# Sheet1.net
KiCad netlist of a schematic drawn in Altium Designer
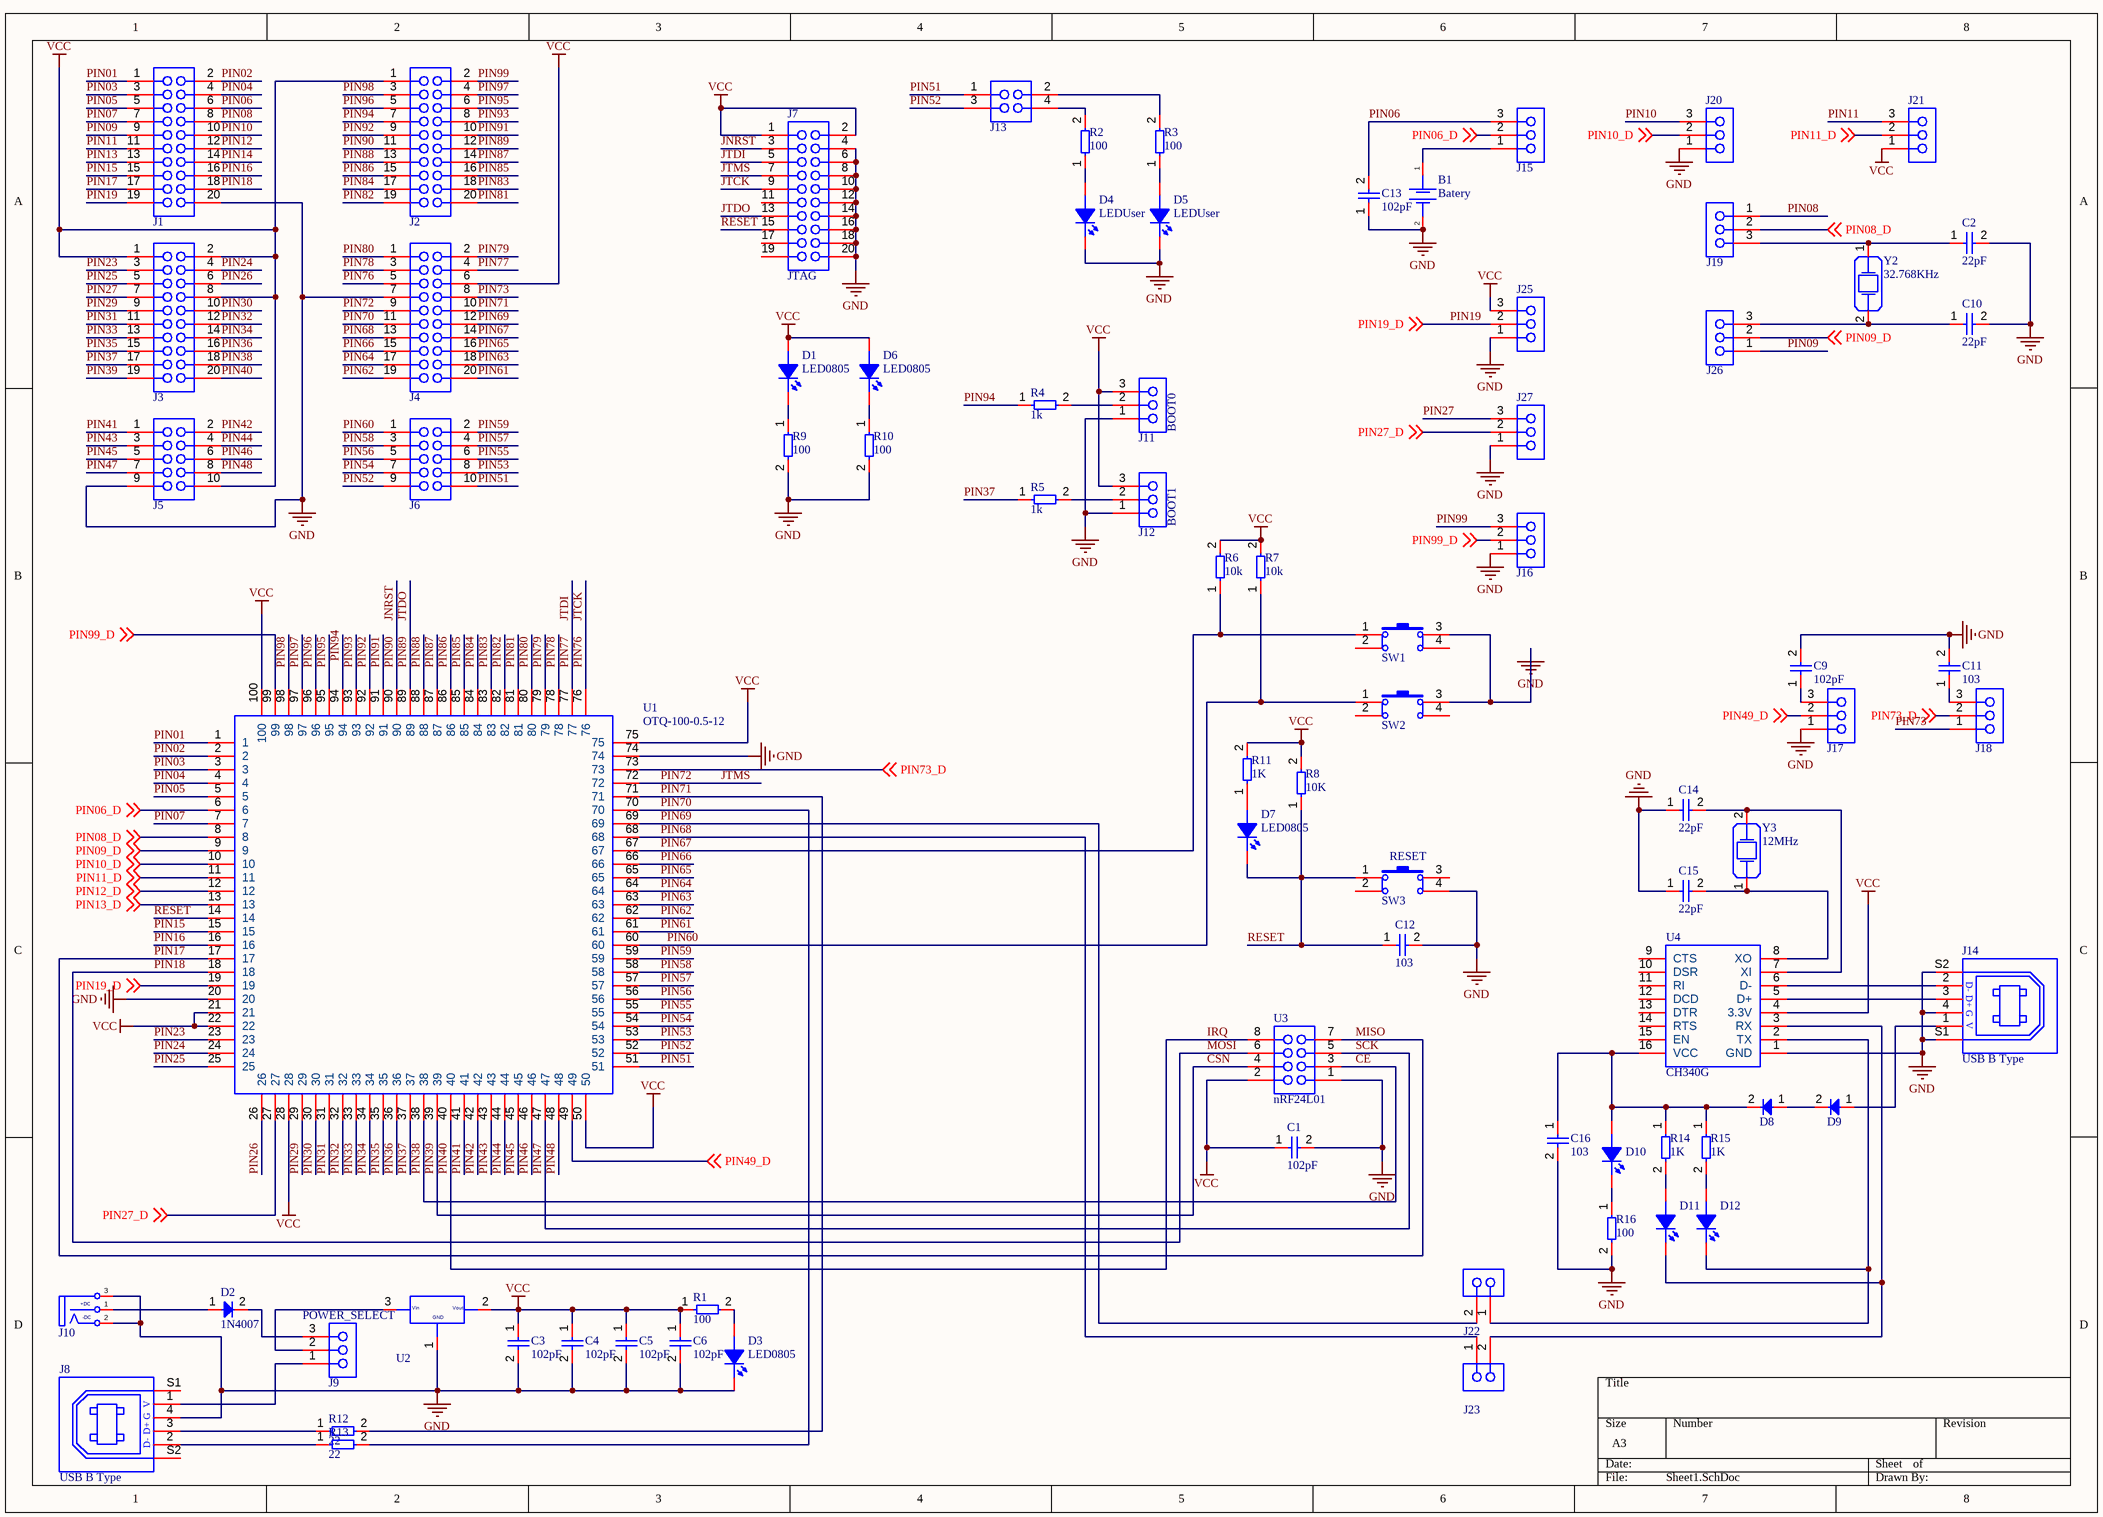
[diagram p0: Sheet1.SchDoc]

(export (version "E")
  (design (tool "Eeschema 10.0.6"))
  (components
    (comp (ref "B1") (value "Batery") (footprint "CR1220") (libsource (lib "SMDLibrary") (part "Batery")))
    (comp (ref "C1")
      (value "102pF")
      (footprint "C1206")
      (libsource (lib "SMDLibrary") (part "Capacitors(SMD)"))
    )
    (comp (ref "C2") (value "22pF") (footprint "C0805") (libsource (lib "SMDLibrary") (part "C0805")))
    (comp (ref "C3")
      (value "102pF")
      (footprint "C0805")
      (libsource (lib "SMDLibrary") (part "Capacitors(SMD)"))
    )
    (comp (ref "C4")
      (value "102pF")
      (footprint "C0805")
      (libsource (lib "SMDLibrary") (part "Capacitors(SMD)"))
    )
    (comp (ref "C5")
      (value "102pF")
      (footprint "C0805")
      (libsource (lib "SMDLibrary") (part "Capacitors(SMD)"))
    )
    (comp (ref "C6")
      (value "102pF")
      (footprint "C0805")
      (libsource (lib "SMDLibrary") (part "Capacitors(SMD)"))
    )
    (comp (ref "C9")
      (value "102pF")
      (footprint "C0805")
      (libsource (lib "SMDLibrary") (part "Capacitors(SMD)"))
    )
    (comp (ref "C10") (value "22pF") (footprint "C0805") (libsource (lib "SMDLibrary") (part "C0805")))
    (comp (ref "C11") (value "103") (footprint "C0805") (libsource (lib "SMDLibrary") (part "C0805")))
    (comp (ref "C12") (value "103") (footprint "C0805") (libsource (lib "SMDLibrary") (part "C0805")))
    (comp (ref "C13")
      (value "102pF")
      (footprint "C0805")
      (libsource (lib "SMDLibrary") (part "Capacitors(SMD)"))
    )
    (comp (ref "C14") (value "22pF") (footprint "C0805") (libsource (lib "SMDLibrary") (part "C0805")))
    (comp (ref "C15") (value "22pF") (footprint "C0805") (libsource (lib "SMDLibrary") (part "C0805")))
    (comp (ref "C16") (value "103") (footprint "C0805") (libsource (lib "SMDLibrary") (part "C0805")))
    (comp (ref "D1") (value "LED0805") (footprint "L0805RED") (libsource (lib "SMDLibrary") (part "LED0805")))
    (comp (ref "D2") (value "1N4007") (footprint "DO-41") (libsource (lib "SMDLibrary") (part "1N4007")))
    (comp (ref "D3") (value "LED0805") (footprint "L0805RED") (libsource (lib "SMDLibrary") (part "LED0805")))
    (comp (ref "D4") (value "LEDUser") (footprint "L0805RED") (libsource (lib "SMDLibrary") (part "LED0805")))
    (comp (ref "D5") (value "LEDUser") (footprint "L0805RED") (libsource (lib "SMDLibrary") (part "LED0805")))
    (comp (ref "D6") (value "LED0805") (footprint "L0805RED") (libsource (lib "SMDLibrary") (part "LED0805")))
    (comp (ref "D7") (value "LED0805") (footprint "L0805RED") (libsource (lib "SMDLibrary") (part "LED0805")))
    (comp (ref "D8")
      (value "1N4148")
      (footprint "SOD-80")
      (libsource (lib "SMDLibrary") (part "1N4148 (SOD-80)"))
    )
    (comp (ref "D9")
      (value "1N4148")
      (footprint "SOD-80")
      (libsource (lib "SMDLibrary") (part "1N4148 (SOD-80)"))
    )
    (comp (ref "D10")
      (value "LED0805")
      (footprint "L0805RED")
      (libsource (lib "SMDLibrary") (part "LED0805"))
    )
    (comp (ref "D11")
      (value "LED0805")
      (footprint "L0805RED")
      (libsource (lib "SMDLibrary") (part "LED0805"))
    )
    (comp (ref "D12")
      (value "LED0805")
      (footprint "L0805RED")
      (libsource (lib "SMDLibrary") (part "LED0805"))
    )
    (comp (ref "J1")
      (value "Header 10x2 TH Pitch 2.54mm")
      (footprint "Header 10x2 TH Pitch 2.54mm")
      (libsource (lib "SMDLibrary") (part "Header 10x2 TH Pitch 2.54mm"))
    )
    (comp (ref "J2")
      (value "Header 10x2 TH Pitch 2.54mm")
      (footprint "Header 10x2 TH Pitch 2.54mm")
      (libsource (lib "SMDLibrary") (part "Header 10x2 TH Pitch 2.54mm"))
    )
    (comp (ref "J3")
      (value "Header 10x2 TH Pitch 2.54mm")
      (footprint "Header 10x2 TH Pitch 2.54mm")
      (libsource (lib "SMDLibrary") (part "Header 10x2 TH Pitch 2.54mm"))
    )
    (comp (ref "J4")
      (value "Header 10x2 TH Pitch 2.54mm")
      (footprint "Header 10x2 TH Pitch 2.54mm")
      (libsource (lib "SMDLibrary") (part "Header 10x2 TH Pitch 2.54mm"))
    )
    (comp (ref "J5")
      (value "Header 5x2 TH Pitch 2.54mm")
      (footprint "Header 5x2 TH Pitch 2.54mm")
      (libsource (lib "SMDLibrary") (part "Header 5x2 TH Pitch 2.54mm"))
    )
    (comp (ref "J6")
      (value "Header 5x2 TH Pitch 2.54mm")
      (footprint "Header 5x2 TH Pitch 2.54mm")
      (libsource (lib "SMDLibrary") (part "Header 5x2 TH Pitch 2.54mm"))
    )
    (comp (ref "J7")
      (value "JTAG")
      (footprint "IDC_CONNECTOR_20_2.54")
      (libsource (lib "SMDLibrary") (part "IDC_2.54_10x2"))
    )
    (comp (ref "J8")
      (value "USB B Type")
      (footprint "USB-B-TYPE")
      (libsource (lib "SMDLibrary") (part "USB B Type"))
    )
    (comp (ref "J9")
      (value "POWER_SELECT")
      (footprint "Header 3x1 TH Pitch 2.54mm")
      (libsource (lib "SMDLibrary") (part "Header 3x1 TH Pitch 2.54mm"))
    )
    (comp (ref "J10")
      (value "Connector")
      (footprint "DC_JACK_161-0721")
      (libsource (lib "SMDLibrary") (part "JackDC"))
    )
    (comp (ref "J11")
      (value "BOOT0")
      (footprint "Header 3x1 TH Pitch 2.54mm")
      (libsource (lib "SMDLibrary") (part "Header 3x1 TH Pitch 2.54mm"))
    )
    (comp (ref "J12")
      (value "BOOT1")
      (footprint "Header 3x1 TH Pitch 2.54mm")
      (libsource (lib "SMDLibrary") (part "Header 3x1 TH Pitch 2.54mm"))
    )
    (comp (ref "J13")
      (value "Header 2x2 TH Pitch 2.54mm")
      (footprint "Header 2x2 TH Pitch 2.54mm")
      (libsource (lib "SMDLibrary") (part "Header 2x2 TH Pitch 2.54mm"))
    )
    (comp (ref "J14")
      (value "USB B Type")
      (footprint "USB-B-TYPE")
      (libsource (lib "") (part "USB B Type_1"))
    )
    (comp (ref "J15")
      (value "Header 3x1 TH Pitch 2.54mm")
      (footprint "Header 3x1 TH Pitch 2.54mm")
      (libsource (lib "SMDLibrary") (part "Header 3x1 TH Pitch 2.54mm"))
    )
    (comp (ref "J16")
      (value "Header 3x1 TH Pitch 2.54mm")
      (footprint "Header 3x1 TH Pitch 2.54mm")
      (libsource (lib "SMDLibrary") (part "Header 3x1 TH Pitch 2.54mm"))
    )
    (comp (ref "J17")
      (value "Header 3x1 TH Pitch 2.54mm")
      (footprint "Header 3x1 TH Pitch 2.54mm")
      (libsource (lib "SMDLibrary") (part "Header 3x1 TH Pitch 2.54mm"))
    )
    (comp (ref "J18")
      (value "Header 3x1 TH Pitch 2.54mm")
      (footprint "Header 3x1 TH Pitch 2.54mm")
      (libsource (lib "SMDLibrary") (part "Header 3x1 TH Pitch 2.54mm"))
    )
    (comp (ref "J19")
      (value "Header 3x1 TH Pitch 2.54mm")
      (footprint "Header 3x1 TH Pitch 2.54mm")
      (libsource (lib "") (part "Header 3x1 TH Pitch 2.54mm_1"))
    )
    (comp (ref "J20")
      (value "Header 3x1 TH Pitch 2.54mm")
      (footprint "Header 3x1 TH Pitch 2.54mm")
      (libsource (lib "SMDLibrary") (part "Header 3x1 TH Pitch 2.54mm"))
    )
    (comp (ref "J21")
      (value "Header 3x1 TH Pitch 2.54mm")
      (footprint "Header 3x1 TH Pitch 2.54mm")
      (libsource (lib "SMDLibrary") (part "Header 3x1 TH Pitch 2.54mm"))
    )
    (comp (ref "J22")
      (value "Header 2x1 TH Pitch 2.54mm")
      (footprint "Header 2x1 TH Pitch 2.54mm")
      (libsource (lib "") (part "Header 2x1 TH Pitch 2.54mm_1"))
    )
    (comp (ref "J23")
      (value "Header 2x1 TH Pitch 2.54mm")
      (footprint "Header 2x1 TH Pitch 2.54mm")
      (libsource (lib "SMDLibrary") (part "Header 2x1 TH Pitch 2.54mm"))
    )
    (comp (ref "J25")
      (value "Header 3x1 TH Pitch 2.54mm")
      (footprint "Header 3x1 TH Pitch 2.54mm")
      (libsource (lib "SMDLibrary") (part "Header 3x1 TH Pitch 2.54mm"))
    )
    (comp (ref "J26")
      (value "Header 3x1 TH Pitch 2.54mm")
      (footprint "Header 3x1 TH Pitch 2.54mm")
      (libsource (lib "") (part "Header 3x1 TH Pitch 2.54mm_2"))
    )
    (comp (ref "J27")
      (value "Header 3x1 TH Pitch 2.54mm")
      (footprint "Header 3x1 TH Pitch 2.54mm")
      (libsource (lib "SMDLibrary") (part "Header 3x1 TH Pitch 2.54mm"))
    )
    (comp (ref "R1") (value "100") (footprint "R0805") (libsource (lib "") (part "R0805_1")))
    (comp (ref "R2") (value "100") (footprint "R0805") (libsource (lib "SMDLibrary") (part "R0805")))
    (comp (ref "R3") (value "100") (footprint "R0805") (libsource (lib "SMDLibrary") (part "R0805")))
    (comp (ref "R4") (value "1k") (footprint "R0805") (libsource (lib "SMDLibrary") (part "Resistor SMD")))
    (comp (ref "R5") (value "1k") (footprint "R0805") (libsource (lib "SMDLibrary") (part "Resistor SMD")))
    (comp (ref "R6") (value "10k") (footprint "R0805") (libsource (lib "") (part "Resistor SMD_1")))
    (comp (ref "R7") (value "10k") (footprint "R0805") (libsource (lib "") (part "Resistor SMD_1")))
    (comp (ref "R8") (value "10K") (footprint "R0805") (libsource (lib "SMDLibrary") (part "R0805")))
    (comp (ref "R9") (value "100") (footprint "R0805") (libsource (lib "") (part "Resistor SMD_2")))
    (comp (ref "R10") (value "100") (footprint "R0805") (libsource (lib "") (part "Resistor SMD_2")))
    (comp (ref "R11") (value "1K") (footprint "R0805") (libsource (lib "") (part "Resistor SMD_1")))
    (comp (ref "R12") (value "22") (footprint "R0805") (libsource (lib "SMDLibrary") (part "Resistor SMD")))
    (comp (ref "R13") (value "22") (footprint "R0805") (libsource (lib "SMDLibrary") (part "Resistor SMD")))
    (comp (ref "R14") (value "1K") (footprint "R0805") (libsource (lib "") (part "R0805_2")))
    (comp (ref "R15") (value "1K") (footprint "R0805") (libsource (lib "") (part "R0805_2")))
    (comp (ref "R16") (value "100") (footprint "R0805") (libsource (lib "") (part "R0805_2")))
    (comp (ref "SW1")
      (value "Button Hole")
      (footprint "BUTTON_HOLE_5.0mm")
      (libsource (lib "SMDLibrary") (part "Button Hole"))
    )
    (comp (ref "SW2")
      (value "Button Hole")
      (footprint "BUTTON_HOLE_5.0mm")
      (libsource (lib "SMDLibrary") (part "Button Hole"))
    )
    (comp (ref "SW3")
      (value "RESET")
      (footprint "BUTTON_HOLE_5.0mm")
      (libsource (lib "SMDLibrary") (part "Button Hole"))
    )
    (comp (ref "U1")
      (value "OTQ-100-0.5-12")
      (footprint "ENPLAS OTQ-100-0.5-12")
      (libsource (lib "SMDLibrary") (part "ENPLAS OTQ-100-0.5-12"))
    )
    (comp (ref "U2")
      (value "AMS1117")
      (footprint "SOT223-3")
      (libsource (lib "SMDLibrary") (part "AMS1117(SOT-223)"))
    )
    (comp (ref "U3")
      (value "nRF24L01")
      (footprint "nRF24L01")
      (libsource (lib "SMDLibrary") (part "nRF24L01"))
    )
    (comp (ref "U4")
      (value "CH340G")
      (footprint "SOP16_1.27_3.8")
      (libsource (lib "SMDLibrary") (part "CH340G"))
    )
    (comp (ref "Y2")
      (value "32.768KHz")
      (footprint "DT-26")
      (libsource (lib "SMDLibrary") (part "Crystal 32.768KHz"))
    )
    (comp (ref "Y3") (value "12MHz") (footprint "SMD5032") (libsource (lib "SMDLibrary") (part "Crystal")))
  )
  (nets
    (net (code "1") (name "/CE") (class "Default")
      (node (ref "J3") (pin "18") (pinfunction "18_18") (pintype "passive"))
      (node (ref "U1") (pin "38") (pinfunction "38_38") (pintype "passive"))
      (node (ref "U3") (pin "3") (pinfunction "3_3") (pintype "passive"))
    )
    (net (code "2") (name "/CSN") (class "Default")
      (node (ref "J3") (pin "19") (pinfunction "19_19") (pintype "passive"))
      (node (ref "U1") (pin "39") (pinfunction "39_39") (pintype "passive"))
      (node (ref "U3") (pin "4") (pinfunction "4_4") (pintype "passive"))
    )
    (net (code "3") (name "/IRQ") (class "Default")
      (node (ref "J3") (pin "20") (pinfunction "20_20") (pintype "passive"))
      (node (ref "U1") (pin "40") (pinfunction "40_40") (pintype "passive"))
      (node (ref "U3") (pin "8") (pinfunction "8_8") (pintype "passive"))
    )
    (net (code "4") (name "/JNRST") (class "Default")
      (node (ref "J2") (pin "11") (pinfunction "11_11") (pintype "passive"))
      (node (ref "J7") (pin "3") (pinfunction "3_3") (pintype "passive"))
      (node (ref "U1") (pin "90") (pinfunction "90_90") (pintype "passive"))
    )
    (net (code "5") (name "/JTCK") (class "Default")
      (node (ref "J4") (pin "5") (pinfunction "5_5") (pintype "passive"))
      (node (ref "J7") (pin "9") (pinfunction "9_9") (pintype "passive"))
      (node (ref "U1") (pin "76") (pinfunction "76_76") (pintype "passive"))
    )
    (net (code "6") (name "/JTDI") (class "Default")
      (node (ref "J4") (pin "4") (pinfunction "4_4") (pintype "passive"))
      (node (ref "J7") (pin "5") (pinfunction "5_5") (pintype "passive"))
      (node (ref "U1") (pin "77") (pinfunction "77_77") (pintype "passive"))
    )
    (net (code "7") (name "/JTDO") (class "Default")
      (node (ref "J2") (pin "12") (pinfunction "12_12") (pintype "passive"))
      (node (ref "J7") (pin "13") (pinfunction "13_13") (pintype "passive"))
      (node (ref "U1") (pin "89") (pinfunction "89_89") (pintype "passive"))
    )
    (net (code "8") (name "/JTMS") (class "Default")
      (node (ref "J4") (pin "9") (pinfunction "9_9") (pintype "passive"))
      (node (ref "J7") (pin "7") (pinfunction "7_7") (pintype "passive"))
      (node (ref "U1") (pin "72") (pinfunction "72_72") (pintype "passive"))
    )
    (net (code "9") (name "/MISO") (class "Default")
      (node (ref "J1") (pin "17") (pinfunction "17_17") (pintype "passive"))
      (node (ref "U1") (pin "17") (pinfunction "17_17") (pintype "passive"))
      (node (ref "U3") (pin "7") (pinfunction "7_7") (pintype "passive"))
    )
    (net (code "10") (name "/MOSI") (class "Default")
      (node (ref "J1") (pin "18") (pinfunction "18_18") (pintype "passive"))
      (node (ref "U1") (pin "18") (pinfunction "18_18") (pintype "passive"))
      (node (ref "U3") (pin "6") (pinfunction "6_6") (pintype "passive"))
    )
    (net (code "11") (name "/PIN01") (class "Default")
      (node (ref "J1") (pin "1") (pinfunction "1_1") (pintype "passive"))
      (node (ref "U1") (pin "1") (pinfunction "1_1") (pintype "passive"))
    )
    (net (code "12") (name "/PIN02") (class "Default")
      (node (ref "J1") (pin "2") (pinfunction "2_2") (pintype "passive"))
      (node (ref "U1") (pin "2") (pinfunction "2_2") (pintype "passive"))
    )
    (net (code "13") (name "/PIN03") (class "Default")
      (node (ref "J1") (pin "3") (pinfunction "3_3") (pintype "passive"))
      (node (ref "U1") (pin "3") (pinfunction "3_3") (pintype "passive"))
    )
    (net (code "14") (name "/PIN04") (class "Default")
      (node (ref "J1") (pin "4") (pinfunction "4_4") (pintype "passive"))
      (node (ref "U1") (pin "4") (pinfunction "4_4") (pintype "passive"))
    )
    (net (code "15") (name "/PIN05") (class "Default")
      (node (ref "J1") (pin "5") (pinfunction "5_5") (pintype "passive"))
      (node (ref "U1") (pin "5") (pinfunction "5_5") (pintype "passive"))
    )
    (net (code "16") (name "/PIN06") (class "Default")
      (node (ref "C13") (pin "2") (pinfunction "2_2") (pintype "passive"))
      (node (ref "J1") (pin "6") (pinfunction "6_6") (pintype "passive"))
      (node (ref "J15") (pin "3") (pinfunction "3_3") (pintype "passive"))
    )
    (net (code "17") (name "/PIN07") (class "Default")
      (node (ref "J1") (pin "7") (pinfunction "7_7") (pintype "passive"))
      (node (ref "U1") (pin "7") (pinfunction "7_7") (pintype "passive"))
    )
    (net (code "18") (name "/PIN08") (class "Default")
      (node (ref "J1") (pin "8") (pinfunction "8_8") (pintype "passive"))
      (node (ref "J19") (pin "1") (pinfunction "1_1") (pintype "passive"))
    )
    (net (code "19") (name "/PIN09") (class "Default")
      (node (ref "J1") (pin "9") (pinfunction "9_9") (pintype "passive"))
      (node (ref "J26") (pin "1") (pinfunction "1_1") (pintype "passive"))
    )
    (net (code "20") (name "/PIN10") (class "Default")
      (node (ref "J1") (pin "10") (pinfunction "10_10") (pintype "passive"))
      (node (ref "J20") (pin "3") (pinfunction "3_3") (pintype "passive"))
    )
    (net (code "21") (name "/PIN11") (class "Default")
      (node (ref "J1") (pin "11") (pinfunction "11_11") (pintype "passive"))
      (node (ref "J21") (pin "3") (pinfunction "3_3") (pintype "passive"))
    )
    (net (code "22") (name "/PIN12") (class "Default")
      (node (ref "J1") (pin "12") (pinfunction "12_12") (pintype "passive"))
    )
    (net (code "23") (name "/PIN13") (class "Default")
      (node (ref "J1") (pin "13") (pinfunction "13_13") (pintype "passive"))
    )
    (net (code "24") (name "/PIN14") (class "Default")
      (node (ref "J1") (pin "14") (pinfunction "14_14") (pintype "passive"))
    )
    (net (code "25") (name "/PIN15") (class "Default")
      (node (ref "J1") (pin "15") (pinfunction "15_15") (pintype "passive"))
      (node (ref "U1") (pin "15") (pinfunction "15_15") (pintype "passive"))
    )
    (net (code "26") (name "/PIN16") (class "Default")
      (node (ref "J1") (pin "16") (pinfunction "16_16") (pintype "passive"))
      (node (ref "U1") (pin "16") (pinfunction "16_16") (pintype "passive"))
    )
    (net (code "27") (name "/PIN23") (class "Default")
      (node (ref "J3") (pin "3") (pinfunction "3_3") (pintype "passive"))
      (node (ref "U1") (pin "23") (pinfunction "23_23") (pintype "passive"))
    )
    (net (code "28") (name "/PIN24") (class "Default")
      (node (ref "J3") (pin "4") (pinfunction "4_4") (pintype "passive"))
      (node (ref "U1") (pin "24") (pinfunction "24_24") (pintype "passive"))
    )
    (net (code "29") (name "/PIN25") (class "Default")
      (node (ref "J3") (pin "5") (pinfunction "5_5") (pintype "passive"))
      (node (ref "U1") (pin "25") (pinfunction "25_25") (pintype "passive"))
    )
    (net (code "30") (name "/PIN26") (class "Default")
      (node (ref "J3") (pin "6") (pinfunction "6_6") (pintype "passive"))
      (node (ref "U1") (pin "26") (pinfunction "26_26") (pintype "passive"))
    )
    (net (code "31") (name "/PIN27") (class "Default")
      (node (ref "J27") (pin "3") (pinfunction "3_3") (pintype "passive"))
      (node (ref "J3") (pin "7") (pinfunction "7_7") (pintype "passive"))
    )
    (net (code "32") (name "/PIN29") (class "Default")
      (node (ref "J3") (pin "9") (pinfunction "9_9") (pintype "passive"))
      (node (ref "U1") (pin "29") (pinfunction "29_29") (pintype "passive"))
    )
    (net (code "33") (name "/PIN30") (class "Default")
      (node (ref "J3") (pin "10") (pinfunction "10_10") (pintype "passive"))
      (node (ref "U1") (pin "30") (pinfunction "30_30") (pintype "passive"))
    )
    (net (code "34") (name "/PIN31") (class "Default")
      (node (ref "J3") (pin "11") (pinfunction "11_11") (pintype "passive"))
      (node (ref "U1") (pin "31") (pinfunction "31_31") (pintype "passive"))
    )
    (net (code "35") (name "/PIN32") (class "Default")
      (node (ref "J3") (pin "12") (pinfunction "12_12") (pintype "passive"))
      (node (ref "U1") (pin "32") (pinfunction "32_32") (pintype "passive"))
    )
    (net (code "36") (name "/PIN33") (class "Default")
      (node (ref "J3") (pin "13") (pinfunction "13_13") (pintype "passive"))
      (node (ref "U1") (pin "33") (pinfunction "33_33") (pintype "passive"))
    )
    (net (code "37") (name "/PIN34") (class "Default")
      (node (ref "J3") (pin "14") (pinfunction "14_14") (pintype "passive"))
      (node (ref "U1") (pin "34") (pinfunction "34_34") (pintype "passive"))
    )
    (net (code "38") (name "/PIN35") (class "Default")
      (node (ref "J3") (pin "15") (pinfunction "15_15") (pintype "passive"))
      (node (ref "U1") (pin "35") (pinfunction "35_35") (pintype "passive"))
    )
    (net (code "39") (name "/PIN36") (class "Default")
      (node (ref "J3") (pin "16") (pinfunction "16_16") (pintype "passive"))
      (node (ref "U1") (pin "36") (pinfunction "36_36") (pintype "passive"))
    )
    (net (code "40") (name "/PIN37") (class "Default")
      (node (ref "J3") (pin "17") (pinfunction "17_17") (pintype "passive"))
      (node (ref "R5") (pin "1") (pinfunction "1_1") (pintype "passive"))
      (node (ref "U1") (pin "37") (pinfunction "37_37") (pintype "passive"))
    )
    (net (code "41") (name "/PIN41") (class "Default")
      (node (ref "J5") (pin "1") (pinfunction "1_1") (pintype "passive"))
      (node (ref "U1") (pin "41") (pinfunction "41_41") (pintype "passive"))
    )
    (net (code "42") (name "/PIN42") (class "Default")
      (node (ref "J5") (pin "2") (pinfunction "2_2") (pintype "passive"))
      (node (ref "U1") (pin "42") (pinfunction "42_42") (pintype "passive"))
    )
    (net (code "43") (name "/PIN43") (class "Default")
      (node (ref "J5") (pin "3") (pinfunction "3_3") (pintype "passive"))
      (node (ref "U1") (pin "43") (pinfunction "43_43") (pintype "passive"))
    )
    (net (code "44") (name "/PIN44") (class "Default")
      (node (ref "J5") (pin "4") (pinfunction "4_4") (pintype "passive"))
      (node (ref "U1") (pin "44") (pinfunction "44_44") (pintype "passive"))
    )
    (net (code "45") (name "/PIN45") (class "Default")
      (node (ref "J5") (pin "5") (pinfunction "5_5") (pintype "passive"))
      (node (ref "U1") (pin "45") (pinfunction "45_45") (pintype "passive"))
    )
    (net (code "46") (name "/PIN46") (class "Default")
      (node (ref "J5") (pin "6") (pinfunction "6_6") (pintype "passive"))
      (node (ref "U1") (pin "46") (pinfunction "46_46") (pintype "passive"))
    )
    (net (code "47") (name "/PIN47") (class "Default")
      (node (ref "J5") (pin "7") (pinfunction "7_7") (pintype "passive"))
      (node (ref "U1") (pin "47") (pinfunction "47_47") (pintype "passive"))
      (node (ref "U3") (pin "5") (pinfunction "5_5") (pintype "passive"))
    )
    (net (code "48") (name "/PIN48") (class "Default")
      (node (ref "J5") (pin "8") (pinfunction "8_8") (pintype "passive"))
      (node (ref "U1") (pin "48") (pinfunction "48_48") (pintype "passive"))
    )
    (net (code "49") (name "/PIN51") (class "Default")
      (node (ref "J13") (pin "1") (pinfunction "1_1") (pintype "passive"))
      (node (ref "J6") (pin "10") (pinfunction "10_10") (pintype "passive"))
      (node (ref "U1") (pin "51") (pinfunction "51_51") (pintype "passive"))
    )
    (net (code "50") (name "/PIN52") (class "Default")
      (node (ref "J13") (pin "3") (pinfunction "3_3") (pintype "passive"))
      (node (ref "J6") (pin "9") (pinfunction "9_9") (pintype "passive"))
      (node (ref "U1") (pin "52") (pinfunction "52_52") (pintype "passive"))
    )
    (net (code "51") (name "/PIN53") (class "Default")
      (node (ref "J6") (pin "8") (pinfunction "8_8") (pintype "passive"))
      (node (ref "U1") (pin "53") (pinfunction "53_53") (pintype "passive"))
    )
    (net (code "52") (name "/PIN54") (class "Default")
      (node (ref "J6") (pin "7") (pinfunction "7_7") (pintype "passive"))
      (node (ref "U1") (pin "54") (pinfunction "54_54") (pintype "passive"))
    )
    (net (code "53") (name "/PIN55") (class "Default")
      (node (ref "J6") (pin "6") (pinfunction "6_6") (pintype "passive"))
      (node (ref "U1") (pin "55") (pinfunction "55_55") (pintype "passive"))
    )
    (net (code "54") (name "/PIN56") (class "Default")
      (node (ref "J6") (pin "5") (pinfunction "5_5") (pintype "passive"))
      (node (ref "U1") (pin "56") (pinfunction "56_56") (pintype "passive"))
    )
    (net (code "55") (name "/PIN57") (class "Default")
      (node (ref "J6") (pin "4") (pinfunction "4_4") (pintype "passive"))
      (node (ref "U1") (pin "57") (pinfunction "57_57") (pintype "passive"))
    )
    (net (code "56") (name "/PIN58") (class "Default")
      (node (ref "J6") (pin "3") (pinfunction "3_3") (pintype "passive"))
      (node (ref "U1") (pin "58") (pinfunction "58_58") (pintype "passive"))
    )
    (net (code "57") (name "/PIN59") (class "Default")
      (node (ref "J6") (pin "2") (pinfunction "2_2") (pintype "passive"))
      (node (ref "U1") (pin "59") (pinfunction "59_59") (pintype "passive"))
    )
    (net (code "58") (name "/PIN60") (class "Default")
      (node (ref "J6") (pin "1") (pinfunction "1_1") (pintype "passive"))
      (node (ref "R7") (pin "1") (pinfunction "1_1") (pintype "passive"))
      (node (ref "SW2") (pin "1") (pinfunction "1_1") (pintype "passive"))
      (node (ref "U1") (pin "60") (pinfunction "60_60") (pintype "passive"))
    )
    (net (code "59") (name "/PIN61") (class "Default")
      (node (ref "J4") (pin "20") (pinfunction "20_20") (pintype "passive"))
      (node (ref "U1") (pin "61") (pinfunction "61_61") (pintype "passive"))
    )
    (net (code "60") (name "/PIN62") (class "Default")
      (node (ref "J4") (pin "19") (pinfunction "19_19") (pintype "passive"))
      (node (ref "U1") (pin "62") (pinfunction "62_62") (pintype "passive"))
    )
    (net (code "61") (name "/PIN63") (class "Default")
      (node (ref "J4") (pin "18") (pinfunction "18_18") (pintype "passive"))
      (node (ref "U1") (pin "63") (pinfunction "63_63") (pintype "passive"))
    )
    (net (code "62") (name "/PIN64") (class "Default")
      (node (ref "J4") (pin "17") (pinfunction "17_17") (pintype "passive"))
      (node (ref "U1") (pin "64") (pinfunction "64_64") (pintype "passive"))
    )
    (net (code "63") (name "/PIN65") (class "Default")
      (node (ref "J4") (pin "16") (pinfunction "16_16") (pintype "passive"))
      (node (ref "U1") (pin "65") (pinfunction "65_65") (pintype "passive"))
    )
    (net (code "64") (name "/PIN66") (class "Default")
      (node (ref "J4") (pin "15") (pinfunction "15_15") (pintype "passive"))
      (node (ref "U1") (pin "66") (pinfunction "66_66") (pintype "passive"))
    )
    (net (code "65") (name "/PIN67") (class "Default")
      (node (ref "J4") (pin "14") (pinfunction "14_14") (pintype "passive"))
      (node (ref "R6") (pin "1") (pinfunction "1_1") (pintype "passive"))
      (node (ref "SW1") (pin "1") (pinfunction "1_1") (pintype "passive"))
      (node (ref "U1") (pin "67") (pinfunction "67_67") (pintype "passive"))
    )
    (net (code "66") (name "/PIN68") (class "Default")
      (node (ref "J23") (pin "1") (pinfunction "1_1") (pintype "passive"))
      (node (ref "J4") (pin "13") (pinfunction "13_13") (pintype "passive"))
      (node (ref "U1") (pin "68") (pinfunction "68_68") (pintype "passive"))
    )
    (net (code "67") (name "/PIN69") (class "Default")
      (node (ref "J22") (pin "2") (pinfunction "2_2") (pintype "passive"))
      (node (ref "J4") (pin "12") (pinfunction "12_12") (pintype "passive"))
      (node (ref "U1") (pin "69") (pinfunction "69_69") (pintype "passive"))
    )
    (net (code "68") (name "/PIN70") (class "Default")
      (node (ref "J4") (pin "11") (pinfunction "11_11") (pintype "passive"))
      (node (ref "R13") (pin "2") (pinfunction "2_2") (pintype "passive"))
      (node (ref "U1") (pin "70") (pinfunction "70_70") (pintype "passive"))
    )
    (net (code "69") (name "/PIN71") (class "Default")
      (node (ref "J4") (pin "10") (pinfunction "10_10") (pintype "passive"))
      (node (ref "R12") (pin "2") (pinfunction "2_2") (pintype "passive"))
      (node (ref "U1") (pin "71") (pinfunction "71_71") (pintype "passive"))
    )
    (net (code "70") (name "/PIN73") (class "Default")
      (node (ref "J18") (pin "1") (pinfunction "1_1") (pintype "passive"))
      (node (ref "J4") (pin "8") (pinfunction "8_8") (pintype "passive"))
    )
    (net (code "71") (name "/PIN78") (class "Default")
      (node (ref "J4") (pin "3") (pinfunction "3_3") (pintype "passive"))
      (node (ref "U1") (pin "78") (pinfunction "78_78") (pintype "passive"))
    )
    (net (code "72") (name "/PIN79") (class "Default")
      (node (ref "J4") (pin "2") (pinfunction "2_2") (pintype "passive"))
      (node (ref "U1") (pin "79") (pinfunction "79_79") (pintype "passive"))
    )
    (net (code "73") (name "/PIN80") (class "Default")
      (node (ref "J4") (pin "1") (pinfunction "1_1") (pintype "passive"))
      (node (ref "U1") (pin "80") (pinfunction "80_80") (pintype "passive"))
    )
    (net (code "74") (name "/PIN81") (class "Default")
      (node (ref "J2") (pin "20") (pinfunction "20_20") (pintype "passive"))
      (node (ref "U1") (pin "81") (pinfunction "81_81") (pintype "passive"))
    )
    (net (code "75") (name "/PIN82") (class "Default")
      (node (ref "J2") (pin "19") (pinfunction "19_19") (pintype "passive"))
      (node (ref "U1") (pin "82") (pinfunction "82_82") (pintype "passive"))
    )
    (net (code "76") (name "/PIN83") (class "Default")
      (node (ref "J2") (pin "18") (pinfunction "18_18") (pintype "passive"))
      (node (ref "U1") (pin "83") (pinfunction "83_83") (pintype "passive"))
    )
    (net (code "77") (name "/PIN84") (class "Default")
      (node (ref "J2") (pin "17") (pinfunction "17_17") (pintype "passive"))
      (node (ref "U1") (pin "84") (pinfunction "84_84") (pintype "passive"))
    )
    (net (code "78") (name "/PIN85") (class "Default")
      (node (ref "J2") (pin "16") (pinfunction "16_16") (pintype "passive"))
      (node (ref "U1") (pin "85") (pinfunction "85_85") (pintype "passive"))
    )
    (net (code "79") (name "/PIN86") (class "Default")
      (node (ref "J2") (pin "15") (pinfunction "15_15") (pintype "passive"))
      (node (ref "U1") (pin "86") (pinfunction "86_86") (pintype "passive"))
    )
    (net (code "80") (name "/PIN87") (class "Default")
      (node (ref "J2") (pin "14") (pinfunction "14_14") (pintype "passive"))
      (node (ref "U1") (pin "87") (pinfunction "87_87") (pintype "passive"))
    )
    (net (code "81") (name "/PIN88") (class "Default")
      (node (ref "J2") (pin "13") (pinfunction "13_13") (pintype "passive"))
      (node (ref "U1") (pin "88") (pinfunction "88_88") (pintype "passive"))
    )
    (net (code "82") (name "/PIN91") (class "Default")
      (node (ref "J2") (pin "10") (pinfunction "10_10") (pintype "passive"))
      (node (ref "U1") (pin "91") (pinfunction "91_91") (pintype "passive"))
    )
    (net (code "83") (name "/PIN92") (class "Default")
      (node (ref "J2") (pin "9") (pinfunction "9_9") (pintype "passive"))
      (node (ref "U1") (pin "92") (pinfunction "92_92") (pintype "passive"))
    )
    (net (code "84") (name "/PIN93") (class "Default")
      (node (ref "J2") (pin "8") (pinfunction "8_8") (pintype "passive"))
      (node (ref "U1") (pin "93") (pinfunction "93_93") (pintype "passive"))
    )
    (net (code "85") (name "/PIN94") (class "Default")
      (node (ref "J2") (pin "7") (pinfunction "7_7") (pintype "passive"))
      (node (ref "R4") (pin "1") (pinfunction "1_1") (pintype "passive"))
      (node (ref "U1") (pin "94") (pinfunction "94_94") (pintype "passive"))
    )
    (net (code "86") (name "/PIN95") (class "Default")
      (node (ref "J2") (pin "6") (pinfunction "6_6") (pintype "passive"))
      (node (ref "U1") (pin "95") (pinfunction "95_95") (pintype "passive"))
    )
    (net (code "87") (name "/PIN96") (class "Default")
      (node (ref "J2") (pin "5") (pinfunction "5_5") (pintype "passive"))
      (node (ref "U1") (pin "96") (pinfunction "96_96") (pintype "passive"))
    )
    (net (code "88") (name "/PIN97") (class "Default")
      (node (ref "J2") (pin "4") (pinfunction "4_4") (pintype "passive"))
      (node (ref "U1") (pin "97") (pinfunction "97_97") (pintype "passive"))
    )
    (net (code "89") (name "/PIN98") (class "Default")
      (node (ref "J2") (pin "3") (pinfunction "3_3") (pintype "passive"))
      (node (ref "U1") (pin "98") (pinfunction "98_98") (pintype "passive"))
    )
    (net (code "90") (name "/PIN99") (class "Default")
      (node (ref "J16") (pin "3") (pinfunction "3_3") (pintype "passive"))
      (node (ref "J2") (pin "2") (pinfunction "2_2") (pintype "passive"))
    )
    (net (code "91") (name "/RESET") (class "Default")
      (node (ref "C12") (pin "1") (pinfunction "1_1") (pintype "passive"))
      (node (ref "D7") (pin "2") (pinfunction "K_2") (pintype "passive"))
      (node (ref "J7") (pin "15") (pinfunction "15_15") (pintype "passive"))
      (node (ref "R8") (pin "1") (pinfunction "1_1") (pintype "passive"))
      (node (ref "SW3") (pin "1") (pinfunction "1_1") (pintype "passive"))
      (node (ref "U1") (pin "14") (pinfunction "14_14") (pintype "passive"))
    )
    (net (code "92") (name "GND") (class "Default")
      (node (ref "B1") (pin "2") (pinfunction "2_2") (pintype "passive"))
      (node (ref "C1") (pin "2") (pinfunction "2_2") (pintype "passive"))
      (node (ref "C10") (pin "2") (pinfunction "2_2") (pintype "passive"))
      (node (ref "C11") (pin "2") (pinfunction "2_2") (pintype "passive"))
      (node (ref "C12") (pin "2") (pinfunction "2_2") (pintype "passive"))
      (node (ref "C13") (pin "1") (pinfunction "1_1") (pintype "passive"))
      (node (ref "C14") (pin "1") (pinfunction "1_1") (pintype "passive"))
      (node (ref "C15") (pin "1") (pinfunction "1_1") (pintype "passive"))
      (node (ref "C16") (pin "2") (pinfunction "2_2") (pintype "passive"))
      (node (ref "C2") (pin "2") (pinfunction "2_2") (pintype "passive"))
      (node (ref "C3") (pin "2") (pinfunction "2_2") (pintype "passive"))
      (node (ref "C4") (pin "2") (pinfunction "2_2") (pintype "passive"))
      (node (ref "C5") (pin "2") (pinfunction "2_2") (pintype "passive"))
      (node (ref "C6") (pin "2") (pinfunction "2_2") (pintype "passive"))
      (node (ref "C9") (pin "2") (pinfunction "2_2") (pintype "passive"))
      (node (ref "D3") (pin "2") (pinfunction "K_2") (pintype "passive"))
      (node (ref "D4") (pin "2") (pinfunction "K_2") (pintype "passive"))
      (node (ref "D5") (pin "2") (pinfunction "K_2") (pintype "passive"))
      (node (ref "J1") (pin "20") (pinfunction "20_20") (pintype "passive"))
      (node (ref "J10") (pin "2") (pinfunction "DC-_2") (pintype "passive"))
      (node (ref "J10") (pin "3") (pinfunction "T_3") (pintype "passive"))
      (node (ref "J11") (pin "1") (pinfunction "1_1") (pintype "passive"))
      (node (ref "J12") (pin "1") (pinfunction "1_1") (pintype "passive"))
      (node (ref "J14") (pin "4") (pinfunction "4_4") (pintype "passive"))
      (node (ref "J14") (pin "S1") (pinfunction "S1_S1") (pintype "passive"))
      (node (ref "J14") (pin "S2") (pinfunction "S2_S2") (pintype "passive"))
      (node (ref "J16") (pin "1") (pinfunction "1_1") (pintype "passive"))
      (node (ref "J17") (pin "1") (pinfunction "1_1") (pintype "passive"))
      (node (ref "J20") (pin "1") (pinfunction "1_1") (pintype "passive"))
      (node (ref "J25") (pin "1") (pinfunction "1_1") (pintype "passive"))
      (node (ref "J27") (pin "1") (pinfunction "1_1") (pintype "passive"))
      (node (ref "J4") (pin "7") (pinfunction "7_7") (pintype "passive"))
      (node (ref "J5") (pin "9") (pinfunction "9_9") (pintype "passive"))
      (node (ref "J7") (pin "10") (pinfunction "10_10") (pintype "passive"))
      (node (ref "J7") (pin "12") (pinfunction "12_12") (pintype "passive"))
      (node (ref "J7") (pin "14") (pinfunction "14_14") (pintype "passive"))
      (node (ref "J7") (pin "16") (pinfunction "16_16") (pintype "passive"))
      (node (ref "J7") (pin "18") (pinfunction "18_18") (pintype "passive"))
      (node (ref "J7") (pin "20") (pinfunction "20_20") (pintype "passive"))
      (node (ref "J7") (pin "4") (pinfunction "4_4") (pintype "passive"))
      (node (ref "J7") (pin "6") (pinfunction "6_6") (pintype "passive"))
      (node (ref "J7") (pin "8") (pinfunction "8_8") (pintype "passive"))
      (node (ref "J8") (pin "4") (pinfunction "4_4") (pintype "passive"))
      (node (ref "R10") (pin "2") (pinfunction "2_2") (pintype "passive"))
      (node (ref "R16") (pin "2") (pinfunction "2_2") (pintype "passive"))
      (node (ref "R9") (pin "2") (pinfunction "2_2") (pintype "passive"))
      (node (ref "SW1") (pin "3") (pinfunction "3_3") (pintype "passive"))
      (node (ref "SW2") (pin "3") (pinfunction "3_3") (pintype "passive"))
      (node (ref "SW3") (pin "4") (pinfunction "4_4") (pintype "passive"))
      (node (ref "U1") (pin "20") (pinfunction "20_20") (pintype "passive"))
      (node (ref "U1") (pin "74") (pinfunction "74_74") (pintype "passive"))
      (node (ref "U2") (pin "1") (pinfunction "1_1") (pintype "passive"))
      (node (ref "U3") (pin "1") (pinfunction "1_1") (pintype "passive"))
      (node (ref "U4") (pin "1") (pinfunction "GND_1") (pintype "passive"))
    )
    (net (code "93") (name "Net-(B1-Pad1)") (class "Default")
      (node (ref "B1") (pin "1") (pinfunction "1_1") (pintype "passive"))
      (node (ref "J15") (pin "1") (pinfunction "1_1") (pintype "passive"))
    )
    (net (code "94") (name "Net-(C2-Pad1)") (class "Default")
      (node (ref "C2") (pin "1") (pinfunction "1_1") (pintype "passive"))
      (node (ref "J19") (pin "3") (pinfunction "3_3") (pintype "passive"))
      (node (ref "Y2") (pin "1") (pinfunction "1_1") (pintype "passive"))
    )
    (net (code "95") (name "Net-(C9-Pad1)") (class "Default")
      (node (ref "C9") (pin "1") (pinfunction "1_1") (pintype "passive"))
      (node (ref "J17") (pin "3") (pinfunction "3_3") (pintype "passive"))
    )
    (net (code "96") (name "Net-(C10-Pad1)") (class "Default")
      (node (ref "C10") (pin "1") (pinfunction "1_1") (pintype "passive"))
      (node (ref "J26") (pin "3") (pinfunction "3_3") (pintype "passive"))
      (node (ref "Y2") (pin "2") (pinfunction "2_2") (pintype "passive"))
    )
    (net (code "97") (name "Net-(C11-Pad1)") (class "Default")
      (node (ref "C11") (pin "1") (pinfunction "1_1") (pintype "passive"))
      (node (ref "J18") (pin "3") (pinfunction "3_3") (pintype "passive"))
    )
    (net (code "98") (name "Net-(D1-K)") (class "Default")
      (node (ref "D1") (pin "2") (pinfunction "K_2") (pintype "passive"))
      (node (ref "R9") (pin "1") (pinfunction "1_1") (pintype "passive"))
    )
    (net (code "99") (name "Net-(D2-Pad2)") (class "Default")
      (node (ref "D2") (pin "2") (pinfunction "2_2") (pintype "passive"))
      (node (ref "J9") (pin "3") (pinfunction "3_3") (pintype "passive"))
    )
    (net (code "100") (name "Net-(D3-A)") (class "Default")
      (node (ref "D3") (pin "1") (pinfunction "A_1") (pintype "passive"))
      (node (ref "R1") (pin "2") (pinfunction "2_2") (pintype "passive"))
    )
    (net (code "101") (name "Net-(D4-A)") (class "Default")
      (node (ref "D4") (pin "1") (pinfunction "A_1") (pintype "passive"))
      (node (ref "R2") (pin "1") (pinfunction "1_1") (pintype "passive"))
    )
    (net (code "102") (name "Net-(D5-A)") (class "Default")
      (node (ref "D5") (pin "1") (pinfunction "A_1") (pintype "passive"))
      (node (ref "R3") (pin "1") (pinfunction "1_1") (pintype "passive"))
    )
    (net (code "103") (name "Net-(D6-K)") (class "Default")
      (node (ref "D6") (pin "2") (pinfunction "K_2") (pintype "passive"))
      (node (ref "R10") (pin "1") (pinfunction "1_1") (pintype "passive"))
    )
    (net (code "104") (name "Net-(D7-A)") (class "Default")
      (node (ref "D7") (pin "1") (pinfunction "A_1") (pintype "passive"))
      (node (ref "R11") (pin "1") (pinfunction "1_1") (pintype "passive"))
    )
    (net (code "105") (name "Net-(D8-Pad1)") (class "Default")
      (node (ref "D8") (pin "1") (pinfunction "1_1") (pintype "passive"))
      (node (ref "D9") (pin "2") (pinfunction "2_2") (pintype "passive"))
    )
    (net (code "106") (name "Net-(D9-Pad1)") (class "Default")
      (node (ref "D9") (pin "1") (pinfunction "1_1") (pintype "passive"))
      (node (ref "J14") (pin "1") (pinfunction "1_1") (pintype "passive"))
    )
    (net (code "107") (name "Net-(D10-A)") (class "Default")
      (node (ref "C16") (pin "1") (pinfunction "1_1") (pintype "passive"))
      (node (ref "D10") (pin "1") (pinfunction "A_1") (pintype "passive"))
      (node (ref "D8") (pin "2") (pinfunction "2_2") (pintype "passive"))
      (node (ref "R14") (pin "1") (pinfunction "1_1") (pintype "passive"))
      (node (ref "R15") (pin "1") (pinfunction "1_1") (pintype "passive"))
      (node (ref "U4") (pin "16") (pinfunction "VCC_16") (pintype "passive"))
    )
    (net (code "108") (name "Net-(D10-K)") (class "Default")
      (node (ref "D10") (pin "2") (pinfunction "K_2") (pintype "passive"))
      (node (ref "R16") (pin "1") (pinfunction "1_1") (pintype "passive"))
    )
    (net (code "109") (name "Net-(D11-A)") (class "Default")
      (node (ref "D11") (pin "1") (pinfunction "A_1") (pintype "passive"))
      (node (ref "R14") (pin "2") (pinfunction "2_2") (pintype "passive"))
    )
    (net (code "110") (name "Net-(D11-K)") (class "Default")
      (node (ref "D11") (pin "2") (pinfunction "K_2") (pintype "passive"))
      (node (ref "J23") (pin "2") (pinfunction "2_2") (pintype "passive"))
      (node (ref "U4") (pin "3") (pinfunction "RX_3") (pintype "passive"))
    )
    (net (code "111") (name "Net-(D12-A)") (class "Default")
      (node (ref "D12") (pin "1") (pinfunction "A_1") (pintype "passive"))
      (node (ref "R15") (pin "2") (pinfunction "2_2") (pintype "passive"))
    )
    (net (code "112") (name "Net-(D12-K)") (class "Default")
      (node (ref "D12") (pin "2") (pinfunction "K_2") (pintype "passive"))
      (node (ref "J22") (pin "1") (pinfunction "1_1") (pintype "passive"))
      (node (ref "U4") (pin "2") (pinfunction "TX_2") (pintype "passive"))
    )
    (net (code "113") (name "Net-(J8-Pad1)") (class "Default")
      (node (ref "J8") (pin "1") (pinfunction "1_1") (pintype "passive"))
      (node (ref "J9") (pin "1") (pinfunction "1_1") (pintype "passive"))
    )
    (net (code "114") (name "Net-(J8-Pad2)") (class "Default")
      (node (ref "J8") (pin "2") (pinfunction "2_2") (pintype "passive"))
      (node (ref "R13") (pin "1") (pinfunction "1_1") (pintype "passive"))
    )
    (net (code "115") (name "Net-(J8-Pad3)") (class "Default")
      (node (ref "J8") (pin "3") (pinfunction "3_3") (pintype "passive"))
      (node (ref "R12") (pin "1") (pinfunction "1_1") (pintype "passive"))
    )
    (net (code "116") (name "Net-(J9-Pad2)") (class "Default")
      (node (ref "J9") (pin "2") (pinfunction "2_2") (pintype "passive"))
      (node (ref "U2") (pin "3") (pinfunction "3_3") (pintype "passive"))
    )
    (net (code "117") (name "Net-(J10-DS+)") (class "Default")
      (node (ref "D2") (pin "1") (pinfunction "1_1") (pintype "passive"))
      (node (ref "J10") (pin "1") (pinfunction "DS+_1") (pintype "power_in"))
    )
    (net (code "118") (name "Net-(J11-Pad2)") (class "Default")
      (node (ref "J11") (pin "2") (pinfunction "2_2") (pintype "passive"))
      (node (ref "R4") (pin "2") (pinfunction "2_2") (pintype "passive"))
    )
    (net (code "119") (name "Net-(J12-Pad2)") (class "Default")
      (node (ref "J12") (pin "2") (pinfunction "2_2") (pintype "passive"))
      (node (ref "R5") (pin "2") (pinfunction "2_2") (pintype "passive"))
    )
    (net (code "120") (name "Net-(J13-Pad2)") (class "Default")
      (node (ref "J13") (pin "2") (pinfunction "2_2") (pintype "passive"))
      (node (ref "R3") (pin "2") (pinfunction "2_2") (pintype "passive"))
    )
    (net (code "121") (name "Net-(J13-Pad4)") (class "Default")
      (node (ref "J13") (pin "4") (pinfunction "4_4") (pintype "passive"))
      (node (ref "R2") (pin "2") (pinfunction "2_2") (pintype "passive"))
    )
    (net (code "122") (name "Net-(U4-D+)") (class "Default")
      (node (ref "J14") (pin "3") (pinfunction "3_3") (pintype "passive"))
      (node (ref "U4") (pin "5") (pinfunction "D+_5") (pintype "passive"))
    )
    (net (code "123") (name "Net-(U4-D-)") (class "Default")
      (node (ref "J14") (pin "2") (pinfunction "2_2") (pintype "passive"))
      (node (ref "U4") (pin "6") (pinfunction "D-_6") (pintype "passive"))
    )
    (net (code "124") (name "Net-(U4-XI)") (class "Default")
      (node (ref "C14") (pin "2") (pinfunction "2_2") (pintype "passive"))
      (node (ref "U4") (pin "7") (pinfunction "XI_7") (pintype "passive"))
      (node (ref "Y3") (pin "2") (pinfunction "2_2") (pintype "passive"))
    )
    (net (code "125") (name "Net-(U4-XO)") (class "Default")
      (node (ref "C15") (pin "2") (pinfunction "2_2") (pintype "passive"))
      (node (ref "U4") (pin "8") (pinfunction "XO_8") (pintype "passive"))
      (node (ref "Y3") (pin "1") (pinfunction "1_1") (pintype "passive"))
    )
    (net (code "126") (name "PIN06_D") (class "Default")
      (node (ref "J15") (pin "2") (pinfunction "2_2") (pintype "passive"))
      (node (ref "U1") (pin "6") (pinfunction "6_6") (pintype "passive"))
    )
    (net (code "127") (name "PIN08_D") (class "Default")
      (node (ref "J19") (pin "2") (pinfunction "2_2") (pintype "passive"))
      (node (ref "U1") (pin "8") (pinfunction "8_8") (pintype "passive"))
    )
    (net (code "128") (name "PIN09_D") (class "Default")
      (node (ref "J26") (pin "2") (pinfunction "2_2") (pintype "passive"))
      (node (ref "U1") (pin "9") (pinfunction "9_9") (pintype "passive"))
    )
    (net (code "129") (name "PIN10_D") (class "Default")
      (node (ref "J20") (pin "2") (pinfunction "2_2") (pintype "passive"))
      (node (ref "U1") (pin "10") (pinfunction "10_10") (pintype "passive"))
    )
    (net (code "130") (name "PIN11_D") (class "Default")
      (node (ref "J21") (pin "2") (pinfunction "2_2") (pintype "passive"))
      (node (ref "U1") (pin "11") (pinfunction "11_11") (pintype "passive"))
    )
    (net (code "131") (name "PIN12_D") (class "Default")
      (node (ref "U1") (pin "12") (pinfunction "12_12") (pintype "passive"))
    )
    (net (code "132") (name "PIN13_D") (class "Default")
      (node (ref "U1") (pin "13") (pinfunction "13_13") (pintype "passive"))
    )
    (net (code "133") (name "PIN19_D") (class "Default")
      (node (ref "J1") (pin "19") (pinfunction "19_19") (pintype "passive"))
      (node (ref "J25") (pin "2") (pinfunction "2_2") (pintype "passive"))
      (node (ref "U1") (pin "19") (pinfunction "19_19") (pintype "passive"))
    )
    (net (code "134") (name "PIN27_D") (class "Default")
      (node (ref "J27") (pin "2") (pinfunction "2_2") (pintype "passive"))
      (node (ref "U1") (pin "27") (pinfunction "27_27") (pintype "passive"))
    )
    (net (code "135") (name "PIN49_D") (class "Default")
      (node (ref "J17") (pin "2") (pinfunction "2_2") (pintype "passive"))
      (node (ref "U1") (pin "49") (pinfunction "49_49") (pintype "passive"))
    )
    (net (code "136") (name "PIN73_D") (class "Default")
      (node (ref "J18") (pin "2") (pinfunction "2_2") (pintype "passive"))
      (node (ref "U1") (pin "73") (pinfunction "73_73") (pintype "passive"))
    )
    (net (code "137") (name "PIN99_D") (class "Default")
      (node (ref "J16") (pin "2") (pinfunction "2_2") (pintype "passive"))
      (node (ref "U1") (pin "99") (pinfunction "99_99") (pintype "passive"))
    )
    (net (code "138") (name "VCC") (class "Default")
      (node (ref "C1") (pin "1") (pinfunction "1_1") (pintype "passive"))
      (node (ref "C3") (pin "1") (pinfunction "1_1") (pintype "passive"))
      (node (ref "C4") (pin "1") (pinfunction "1_1") (pintype "passive"))
      (node (ref "C5") (pin "1") (pinfunction "1_1") (pintype "passive"))
      (node (ref "C6") (pin "1") (pinfunction "1_1") (pintype "passive"))
      (node (ref "D1") (pin "1") (pinfunction "A_1") (pintype "passive"))
      (node (ref "D6") (pin "1") (pinfunction "A_1") (pintype "passive"))
      (node (ref "J11") (pin "3") (pinfunction "3_3") (pintype "passive"))
      (node (ref "J12") (pin "3") (pinfunction "3_3") (pintype "passive"))
      (node (ref "J2") (pin "1") (pinfunction "1_1") (pintype "passive"))
      (node (ref "J21") (pin "1") (pinfunction "1_1") (pintype "passive"))
      (node (ref "J25") (pin "3") (pinfunction "3_3") (pintype "passive"))
      (node (ref "J3") (pin "1") (pinfunction "1_1") (pintype "passive"))
      (node (ref "J3") (pin "2") (pinfunction "2_2") (pintype "passive"))
      (node (ref "J3") (pin "8") (pinfunction "8_8") (pintype "passive"))
      (node (ref "J4") (pin "6") (pinfunction "6_6") (pintype "passive"))
      (node (ref "J5") (pin "10") (pinfunction "10_10") (pintype "passive"))
      (node (ref "J7") (pin "1") (pinfunction "1_1") (pintype "passive"))
      (node (ref "J7") (pin "2") (pinfunction "2_2") (pintype "passive"))
      (node (ref "R1") (pin "1") (pinfunction "1_1") (pintype "passive"))
      (node (ref "R11") (pin "2") (pinfunction "2_2") (pintype "passive"))
      (node (ref "R6") (pin "2") (pinfunction "2_2") (pintype "passive"))
      (node (ref "R7") (pin "2") (pinfunction "2_2") (pintype "passive"))
      (node (ref "R8") (pin "2") (pinfunction "2_2") (pintype "passive"))
      (node (ref "U1") (pin "100") (pinfunction "100_100") (pintype "passive"))
      (node (ref "U1") (pin "21") (pinfunction "21_21") (pintype "passive"))
      (node (ref "U1") (pin "22") (pinfunction "22_22") (pintype "passive"))
      (node (ref "U1") (pin "28") (pinfunction "28_28") (pintype "passive"))
      (node (ref "U1") (pin "50") (pinfunction "50_50") (pintype "passive"))
      (node (ref "U1") (pin "75") (pinfunction "75_75") (pintype "passive"))
      (node (ref "U2") (pin "2") (pinfunction "2_2") (pintype "passive"))
      (node (ref "U3") (pin "2") (pinfunction "2_2") (pintype "passive"))
      (node (ref "U4") (pin "4") (pinfunction "3.3V_4") (pintype "passive"))
    )
    (net (code "139") (name "unconnected-(J7-Pad11)") (class "Default")
      (node (ref "J7") (pin "11") (pinfunction "11_11") (pintype "passive"))
    )
    (net (code "140") (name "unconnected-(J7-Pad17)") (class "Default")
      (node (ref "J7") (pin "17") (pinfunction "17_17") (pintype "passive"))
    )
    (net (code "141") (name "unconnected-(J7-Pad19)") (class "Default")
      (node (ref "J7") (pin "19") (pinfunction "19_19") (pintype "passive"))
    )
    (net (code "142") (name "unconnected-(J8-PadS1)") (class "Default")
      (node (ref "J8") (pin "S1") (pinfunction "S1_S1") (pintype "passive"))
    )
    (net (code "143") (name "unconnected-(J8-PadS2)") (class "Default")
      (node (ref "J8") (pin "S2") (pinfunction "S2_S2") (pintype "passive"))
    )
    (net (code "144") (name "unconnected-(SW1-Pad2)") (class "Default")
      (node (ref "SW1") (pin "2") (pinfunction "2_2") (pintype "passive"))
    )
    (net (code "145") (name "unconnected-(SW1-Pad4)") (class "Default")
      (node (ref "SW1") (pin "4") (pinfunction "4_4") (pintype "passive"))
    )
    (net (code "146") (name "unconnected-(SW2-Pad2)") (class "Default")
      (node (ref "SW2") (pin "2") (pinfunction "2_2") (pintype "passive"))
    )
    (net (code "147") (name "unconnected-(SW2-Pad4)") (class "Default")
      (node (ref "SW2") (pin "4") (pinfunction "4_4") (pintype "passive"))
    )
    (net (code "148") (name "unconnected-(SW3-Pad2)") (class "Default")
      (node (ref "SW3") (pin "2") (pinfunction "2_2") (pintype "passive"))
    )
    (net (code "149") (name "unconnected-(SW3-Pad3)") (class "Default")
      (node (ref "SW3") (pin "3") (pinfunction "3_3") (pintype "passive"))
    )
    (net (code "150") (name "unconnected-(U4-CTS-Pad9)") (class "Default")
      (node (ref "U4") (pin "9") (pinfunction "CTS_9") (pintype "passive"))
    )
    (net (code "151") (name "unconnected-(U4-DCD-Pad12)") (class "Default")
      (node (ref "U4") (pin "12") (pinfunction "DCD_12") (pintype "passive"))
    )
    (net (code "152") (name "unconnected-(U4-DSR-Pad10)") (class "Default")
      (node (ref "U4") (pin "10") (pinfunction "DSR_10") (pintype "passive"))
    )
    (net (code "153") (name "unconnected-(U4-DTR-Pad13)") (class "Default")
      (node (ref "U4") (pin "13") (pinfunction "DTR_13") (pintype "passive"))
    )
    (net (code "154") (name "unconnected-(U4-EN-Pad15)") (class "Default")
      (node (ref "U4") (pin "15") (pinfunction "EN_15") (pintype "passive"))
    )
    (net (code "155") (name "unconnected-(U4-RI-Pad11)") (class "Default")
      (node (ref "U4") (pin "11") (pinfunction "RI_11") (pintype "passive"))
    )
    (net (code "156") (name "unconnected-(U4-RTS-Pad14)") (class "Default")
      (node (ref "U4") (pin "14") (pinfunction "RTS_14") (pintype "passive"))
    )
  )
)
